# PCB_-RY-Serial.net
KiCad netlist of a schematic drawn in EasyEDA Pro
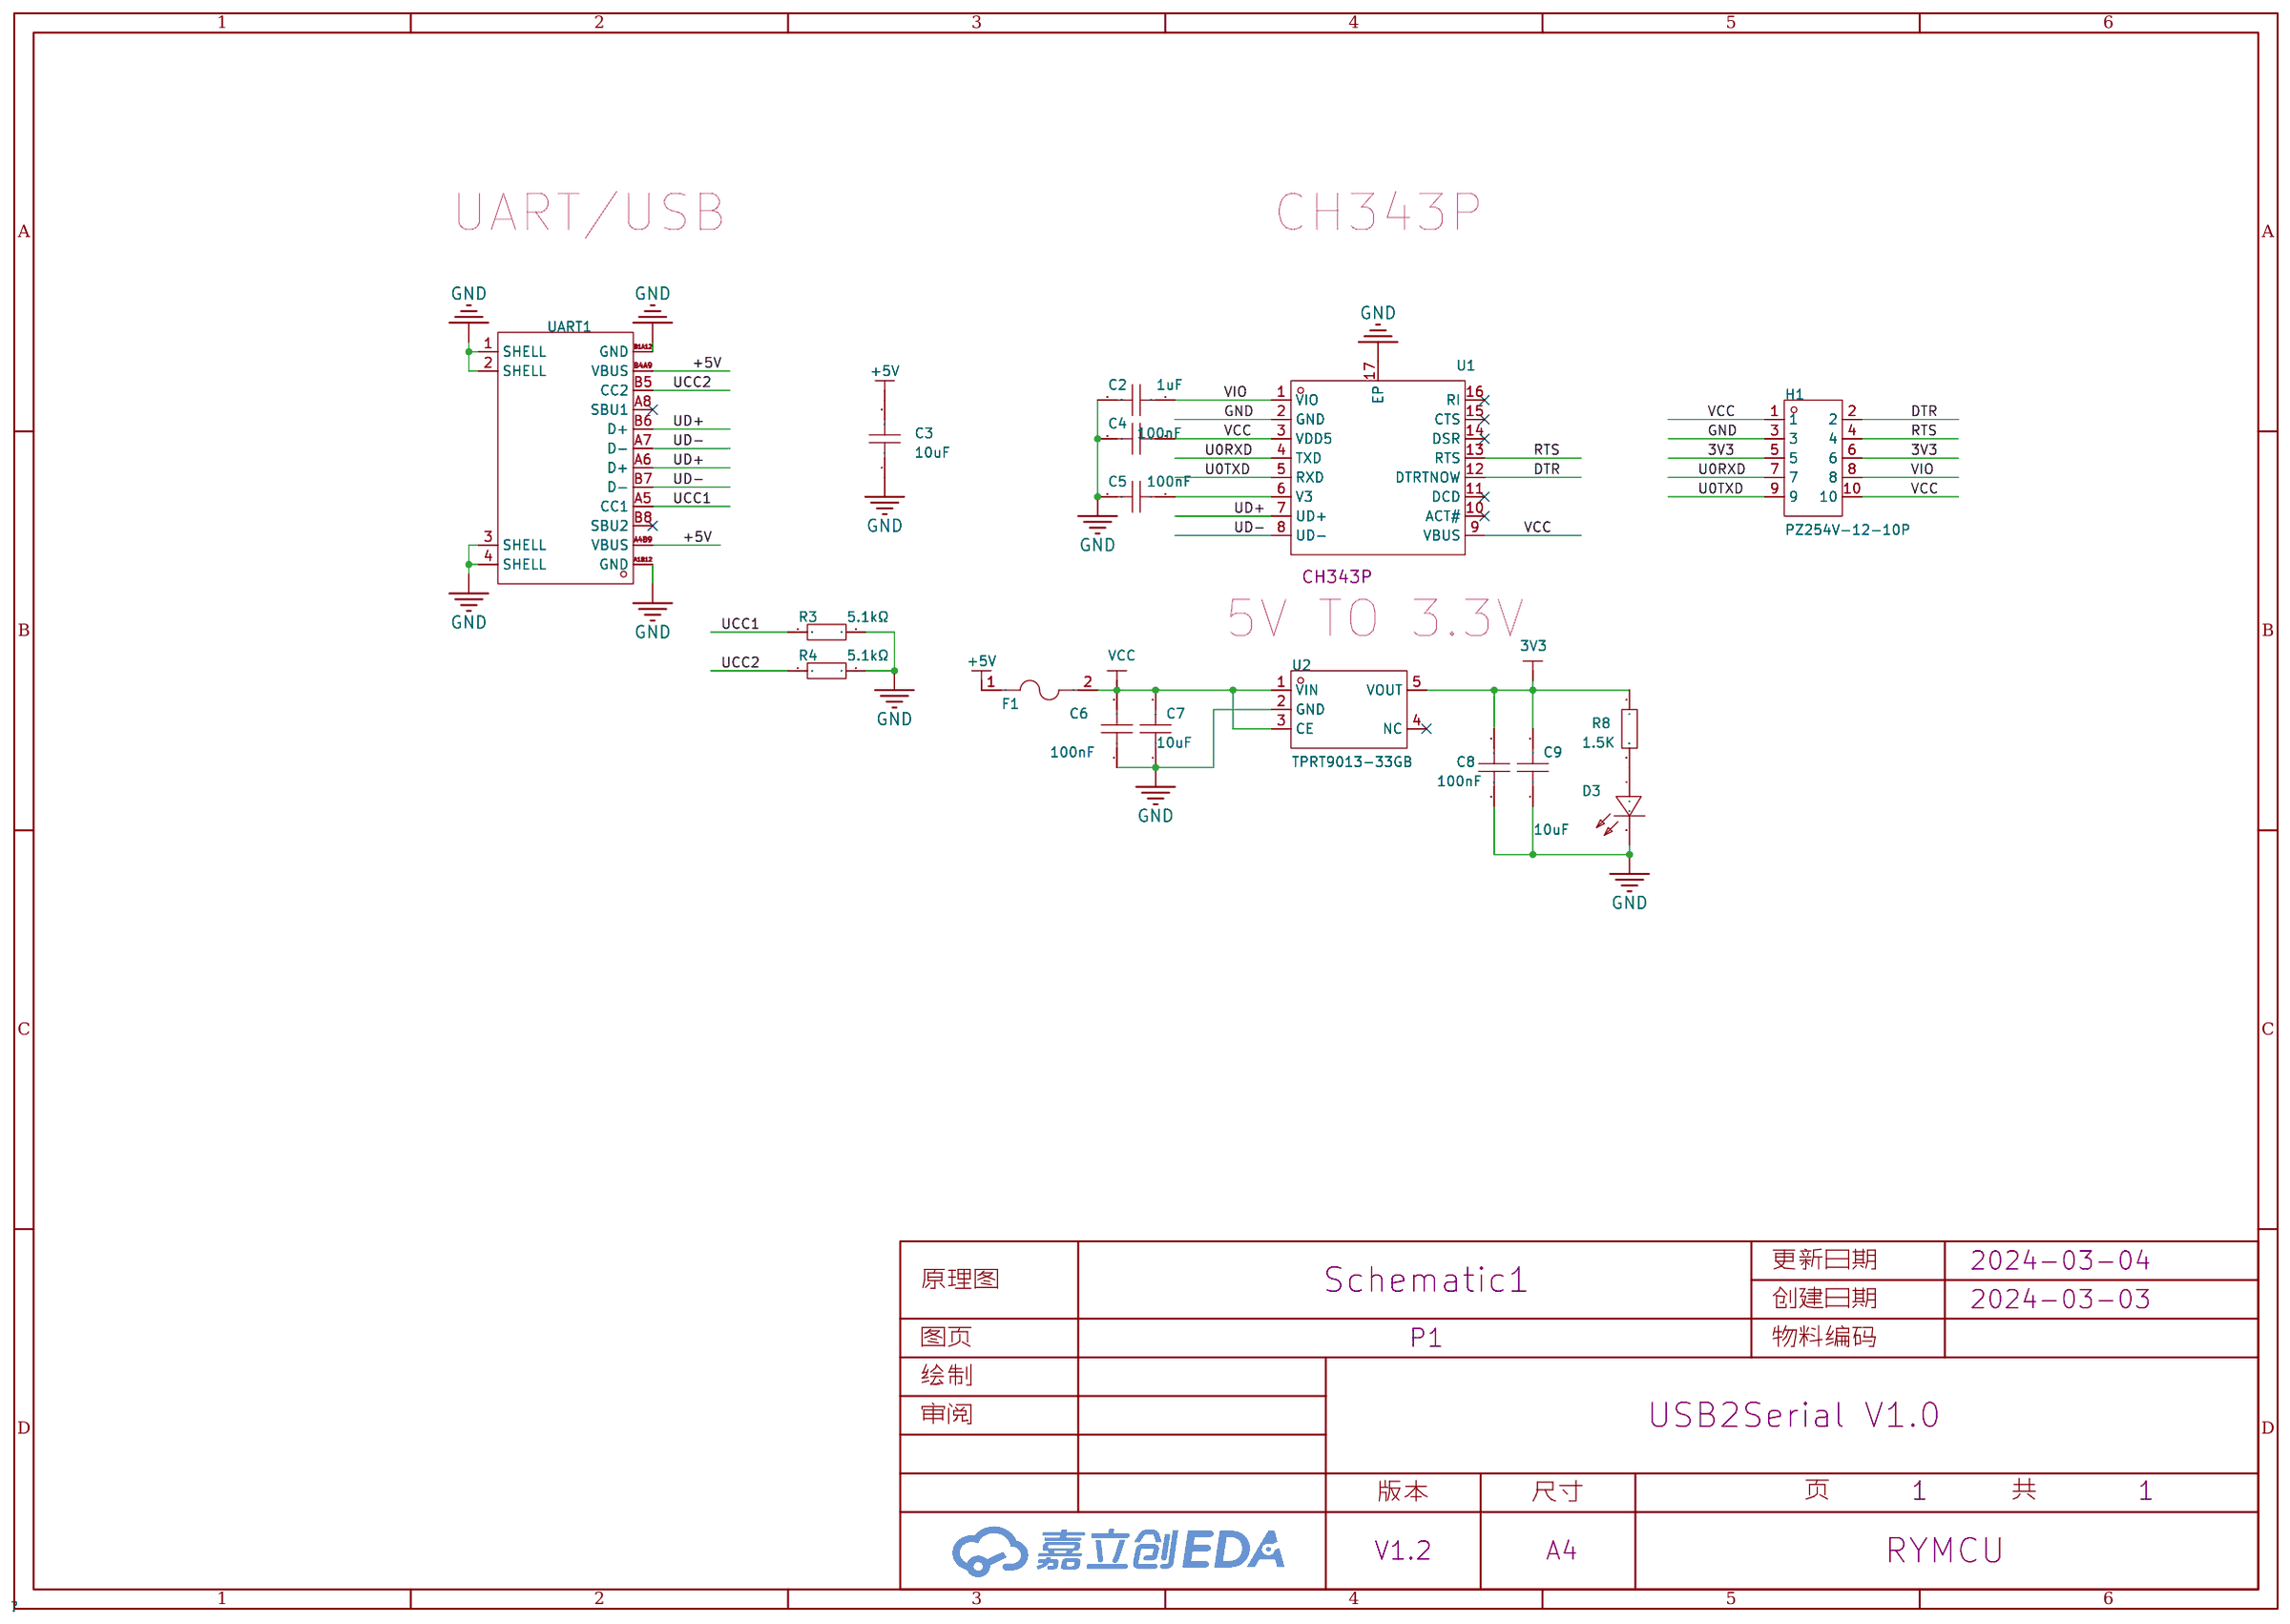
[diagram p0: schematic sheet]

(export (version "E")
  (design (tool "Eeschema 10.0.6"))
  (components
    (comp (ref "C2")
      (value "1uF")
      (fields
        (field (name "Manufacturer Part") "CC0603KRX7R9BB104")
        (field (name "Manufacturer") "YAGEO(国巨)")
      )
      (libsource (lib "easyedapro") (part "CC0603KRX7R9BB104"))
    )
    (comp (ref "C3")
      (value "10uF")
      (fields
        (field (name "Manufacturer Part") "CC0805FRNPO9BN330")
        (field (name "Manufacturer") "YAGEO(国巨)")
      )
      (libsource (lib "easyedapro") (part "CC0805FRNPO9BN330"))
    )
    (comp (ref "C4")
      (value "100nF")
      (fields
        (field (name "Manufacturer Part") "CC0603KRX7R9BB104")
        (field (name "Manufacturer") "YAGEO(国巨)")
      )
      (libsource (lib "easyedapro") (part "CC0603KRX7R9BB104"))
    )
    (comp (ref "C5")
      (value "100nF")
      (fields
        (field (name "Manufacturer Part") "CC0603KRX7R9BB104")
        (field (name "Manufacturer") "YAGEO(国巨)")
      )
      (libsource (lib "easyedapro") (part "CC0603KRX7R9BB104"))
    )
    (comp (ref "C6")
      (value "100nF")
      (footprint "easyedapro:C0603")
      (description "容值:100nF;精度:±10%;额定电压:50V;材质(温度系数):X7R;")
      (fields
        (field (name "Manufacturer Part") "CC0603KRX7R9BB104")
        (field (name "Manufacturer") "YAGEO(国巨)")
      )
      (libsource (lib "easyedapro") (part "CC0603KRX7R9BB104"))
    )
    (comp (ref "C7")
      (value "10uF")
      (fields
        (field (name "Manufacturer Part") "CC0805FRNPO9BN330")
        (field (name "Manufacturer") "YAGEO(国巨)")
      )
      (libsource (lib "easyedapro") (part "CC0805FRNPO9BN330"))
    )
    (comp (ref "C8")
      (value "100nF")
      (footprint "easyedapro:C0603")
      (description "容值:100nF;精度:±10%;额定电压:50V;材质(温度系数):X7R;")
      (fields
        (field (name "Manufacturer Part") "CC0603KRX7R9BB104")
        (field (name "Manufacturer") "YAGEO(国巨)")
      )
      (libsource (lib "easyedapro") (part "CC0603KRX7R9BB104"))
    )
    (comp (ref "C9")
      (value "10uF")
      (fields
        (field (name "Manufacturer Part") "CC0805FRNPO9BN330")
        (field (name "Manufacturer") "YAGEO(国巨)")
      )
      (libsource (lib "easyedapro") (part "CC0805FRNPO9BN330"))
    )
    (comp (ref "D3")
      (value "NCD0603R3")
      (footprint "easyedapro:LED0603-R-RD_RED")
      (description "尺寸1.6x0.8x0.8；IF=20ma：1.6~2.6v，620~640nm,51~150mcd金线，光强高，功耗低，可靠性好，寿命长")
      (fields (field (name "Manufacturer") "国星光电"))
      (libsource (lib "easyedapro") (part "NCD0603R3"))
    )
    (comp (ref "F1")
      (value "~")
      (footprint "easyedapro:F0805")
      (fields (field (name "Manufacturer Part") "ASMD0805-075") (field (name "Manufacturer") "JDTfuse集电通"))
      (libsource (lib "easyedapro") (part "ASMD0805-075"))
    )
    (comp (ref "H1")
      (value "PZ254V-12-10P")
      (footprint "easyedapro:HDR-TH_10P-P2.54-V-M-R2-C5-S2.54")
      (fields (field (name "Manufacturer") "XFCN(兴飞)"))
      (libsource (lib "easyedapro") (part "PZ254V-12-10P"))
    )
    (comp (ref "R3")
      (value "5.1kΩ")
      (footprint "easyedapro:R0603")
      (description "阻值:5.1kΩ;精度:±1%;功率:100mW;温度系数:±100ppm/°C;电阻类型:厚膜电阻;")
      (fields
        (field (name "Manufacturer Part") "0603WAF5101T5E")
        (field (name "Manufacturer") "UNI-ROYAL(厚声)")
      )
      (libsource (lib "easyedapro") (part "0603WAF5101T5E"))
    )
    (comp (ref "R4")
      (value "5.1kΩ")
      (footprint "easyedapro:R0603")
      (description "阻值:5.1kΩ;精度:±1%;功率:100mW;温度系数:±100ppm/°C;电阻类型:厚膜电阻;")
      (fields
        (field (name "Manufacturer Part") "0603WAF5101T5E")
        (field (name "Manufacturer") "UNI-ROYAL(厚声)")
      )
      (libsource (lib "easyedapro") (part "0603WAF5101T5E"))
    )
    (comp (ref "R8")
      (value "1.5K")
      (footprint "easyedapro:R0603")
      (description "电阻类型:薄膜电阻;阻值:10kΩ;精度:±0.1%;功率:100mW;温度系数:±25ppm/;最大工作电压:75V;工作温度范围:-55~+155;")
      (fields
        (field (name "Manufacturer Part") "TR0603B10K0P0525Z")
        (field (name "Manufacturer") "EVER OHMS(天二科技)")
      )
      (libsource (lib "easyedapro") (part "TR0603B10KP05250.1W"))
    )
    (comp (ref "U1")
      (value "CH343P")
      (footprint "easyedapro:TQFN-16_L3.0-W3.0-P0.50-BL-EP1.7")
      (description "类型:-;协议类别:-;驱动器/接收器数:-;数据速率:-;")
      (fields (field (name "Manufacturer") "WCH(南京沁恒)") (field (name "LCSC Part Name") "CH343P"))
      (libsource (lib "easyedapro") (part "CH343P"))
    )
    (comp (ref "U2")
      (value "TPRT9013-33GB")
      (footprint "easyedapro:SOT-23-5_L3.0-W1.7-P0.95-LS2.8-BL")
      (description "输出类型:-;")
      (fields (field (name "Manufacturer") "TECH PUBLIC(台舟)"))
      (libsource (lib "easyedapro") (part "TPRT9013-33GB"))
    )
    (comp (ref "UART1")
      (value "~")
      (footprint "easyedapro:USB-C-SMD_G-SWITCH_GT-USB-7010EN")
      (description "连接器类型:Type-C;公母:母座;触点数量:16;端口数量:1;安装方式:卧贴;")
      (fields
        (field (name "Manufacturer Part") "HC-TYPE-C-16P-01A-R")
        (field (name "Manufacturer") "HCTL(华灿天禄)")
      )
      (libsource (lib "easyedapro") (part "HC-TYPE-C-16P-01A-R"))
    )
  )
  (nets
    (net (code "1") (name "+5V") (class "Default")
      (node (ref "C3") (pin "2") (pinfunction "2_2") (pintype "input"))
      (node (ref "F1") (pin "1") (pinfunction "1_1") (pintype "input"))
      (node (ref "UART1") (pin "A4B9") (pinfunction "VBUS_A4B9") (pintype "input"))
      (node (ref "UART1") (pin "B4A9") (pinfunction "VBUS_B4A9") (pintype "input"))
    )
    (net (code "2") (name "/DTR") (class "Default")
      (node (ref "H1") (pin "2") (pinfunction "2_2") (pintype "unspecified"))
      (node (ref "U1") (pin "12") (pinfunction "DTRTNOW_12") (pintype "input"))
    )
    (net (code "3") (name "/RTS") (class "Default")
      (node (ref "H1") (pin "4") (pinfunction "4_4") (pintype "unspecified"))
      (node (ref "U1") (pin "13") (pinfunction "RTS_13") (pintype "input"))
    )
    (net (code "4") (name "/U0RXD") (class "Default")
      (node (ref "H1") (pin "7") (pinfunction "7_7") (pintype "unspecified"))
      (node (ref "U1") (pin "4") (pinfunction "TXD_4") (pintype "input"))
    )
    (net (code "5") (name "/U0TXD") (class "Default")
      (node (ref "H1") (pin "9") (pinfunction "9_9") (pintype "unspecified"))
      (node (ref "U1") (pin "5") (pinfunction "RXD_5") (pintype "input"))
    )
    (net (code "6") (name "/UCC1") (class "Default")
      (node (ref "R3") (pin "1") (pinfunction "1_1") (pintype "input"))
      (node (ref "UART1") (pin "A5") (pinfunction "CC1_A5") (pintype "input"))
    )
    (net (code "7") (name "/UCC2") (class "Default")
      (node (ref "R4") (pin "1") (pinfunction "1_1") (pintype "input"))
      (node (ref "UART1") (pin "B5") (pinfunction "CC2_B5") (pintype "input"))
    )
    (net (code "8") (name "/UD+") (class "Default")
      (node (ref "U1") (pin "7") (pinfunction "UD+_7") (pintype "input"))
      (node (ref "UART1") (pin "A6") (pinfunction "D+_A6") (pintype "input"))
      (node (ref "UART1") (pin "B6") (pinfunction "D+_B6") (pintype "input"))
    )
    (net (code "9") (name "/UD-") (class "Default")
      (node (ref "U1") (pin "8") (pinfunction "UD-_8") (pintype "input"))
      (node (ref "UART1") (pin "A7") (pinfunction "D-_A7") (pintype "input"))
      (node (ref "UART1") (pin "B7") (pinfunction "D-_B7") (pintype "input"))
    )
    (net (code "10") (name "/VIO") (class "Default")
      (node (ref "C2") (pin "1") (pinfunction "1_1") (pintype "input"))
      (node (ref "H1") (pin "8") (pinfunction "8_8") (pintype "unspecified"))
      (node (ref "U1") (pin "1") (pinfunction "VIO_1") (pintype "input"))
    )
    (net (code "11") (name "3V3") (class "Default")
      (node (ref "C8") (pin "1") (pinfunction "1_1") (pintype "input"))
      (node (ref "C9") (pin "2") (pinfunction "2_2") (pintype "input"))
      (node (ref "H1") (pin "5") (pinfunction "5_5") (pintype "unspecified"))
      (node (ref "H1") (pin "6") (pinfunction "6_6") (pintype "unspecified"))
      (node (ref "R8") (pin "1") (pinfunction "1_1") (pintype "input"))
      (node (ref "U2") (pin "5") (pinfunction "VOUT_5") (pintype "input"))
    )
    (net (code "12") (name "GND") (class "Default")
      (node (ref "C2") (pin "2") (pinfunction "2_2") (pintype "input"))
      (node (ref "C3") (pin "1") (pinfunction "1_1") (pintype "input"))
      (node (ref "C4") (pin "2") (pinfunction "2_2") (pintype "input"))
      (node (ref "C5") (pin "2") (pinfunction "2_2") (pintype "input"))
      (node (ref "C6") (pin "1") (pinfunction "1_1") (pintype "input"))
      (node (ref "C7") (pin "1") (pinfunction "1_1") (pintype "input"))
      (node (ref "C8") (pin "2") (pinfunction "2_2") (pintype "input"))
      (node (ref "C9") (pin "1") (pinfunction "1_1") (pintype "input"))
      (node (ref "D3") (pin "2") (pinfunction "K_2") (pintype "input"))
      (node (ref "H1") (pin "3") (pinfunction "3_3") (pintype "unspecified"))
      (node (ref "R3") (pin "2") (pinfunction "2_2") (pintype "input"))
      (node (ref "R4") (pin "2") (pinfunction "2_2") (pintype "input"))
      (node (ref "U1") (pin "17") (pinfunction "EP_17") (pintype "input"))
      (node (ref "U1") (pin "2") (pinfunction "GND_2") (pintype "input"))
      (node (ref "U2") (pin "2") (pinfunction "GND_2") (pintype "input"))
      (node (ref "UART1") (pin "1") (pinfunction "SHELL_1") (pintype "input"))
      (node (ref "UART1") (pin "2") (pinfunction "SHELL_2") (pintype "input"))
      (node (ref "UART1") (pin "3") (pinfunction "SHELL_3") (pintype "input"))
      (node (ref "UART1") (pin "4") (pinfunction "SHELL_4") (pintype "input"))
      (node (ref "UART1") (pin "A1B12") (pinfunction "GND_A1B12") (pintype "input"))
      (node (ref "UART1") (pin "B1A12") (pinfunction "GND_B1A12") (pintype "input"))
    )
    (net (code "13") (name "Net-(D3-A)") (class "Default")
      (node (ref "D3") (pin "1") (pinfunction "A_1") (pintype "input"))
      (node (ref "R8") (pin "2") (pinfunction "2_2") (pintype "input"))
    )
    (net (code "14") (name "Net-(U1-V3)") (class "Default")
      (node (ref "C5") (pin "1") (pinfunction "1_1") (pintype "input"))
      (node (ref "U1") (pin "6") (pinfunction "V3_6") (pintype "input"))
    )
    (net (code "15") (name "VCC") (class "Default")
      (node (ref "C4") (pin "1") (pinfunction "1_1") (pintype "input"))
      (node (ref "C6") (pin "2") (pinfunction "2_2") (pintype "input"))
      (node (ref "C7") (pin "2") (pinfunction "2_2") (pintype "input"))
      (node (ref "F1") (pin "2") (pinfunction "2_2") (pintype "input"))
      (node (ref "H1") (pin "1") (pinfunction "1_1") (pintype "unspecified"))
      (node (ref "H1") (pin "10") (pinfunction "10_10") (pintype "unspecified"))
      (node (ref "U1") (pin "3") (pinfunction "VDD5_3") (pintype "input"))
      (node (ref "U1") (pin "9") (pinfunction "VBUS_9") (pintype "input"))
      (node (ref "U2") (pin "1") (pinfunction "VIN_1") (pintype "input"))
      (node (ref "U2") (pin "3") (pinfunction "CE_3") (pintype "input"))
    )
    (net (code "16") (name "unconnected-(U1-ACT#-Pad10)") (class "Default")
      (node (ref "U1") (pin "10") (pinfunction "ACT#_10") (pintype "input+no_connect"))
    )
    (net (code "17") (name "unconnected-(U1-CTS-Pad15)") (class "Default")
      (node (ref "U1") (pin "15") (pinfunction "CTS_15") (pintype "input+no_connect"))
    )
    (net (code "18") (name "unconnected-(U1-DCD-Pad11)") (class "Default")
      (node (ref "U1") (pin "11") (pinfunction "DCD_11") (pintype "input+no_connect"))
    )
    (net (code "19") (name "unconnected-(U1-DSR-Pad14)") (class "Default")
      (node (ref "U1") (pin "14") (pinfunction "DSR_14") (pintype "input+no_connect"))
    )
    (net (code "20") (name "unconnected-(U1-RI-Pad16)") (class "Default")
      (node (ref "U1") (pin "16") (pinfunction "RI_16") (pintype "input+no_connect"))
    )
    (net (code "21") (name "unconnected-(U2-NC-Pad4)") (class "Default")
      (node (ref "U2") (pin "4") (pinfunction "NC_4") (pintype "input+no_connect"))
    )
    (net (code "22") (name "unconnected-(UART1-SBU1-PadA8)") (class "Default")
      (node (ref "UART1") (pin "A8") (pinfunction "SBU1_A8") (pintype "input+no_connect"))
    )
    (net (code "23") (name "unconnected-(UART1-SBU2-PadB8)") (class "Default")
      (node (ref "UART1") (pin "B8") (pinfunction "SBU2_B8") (pintype "input+no_connect"))
    )
  )
)
